# BengalaV1.net
KiCad netlist of a schematic drawn in EAGLE
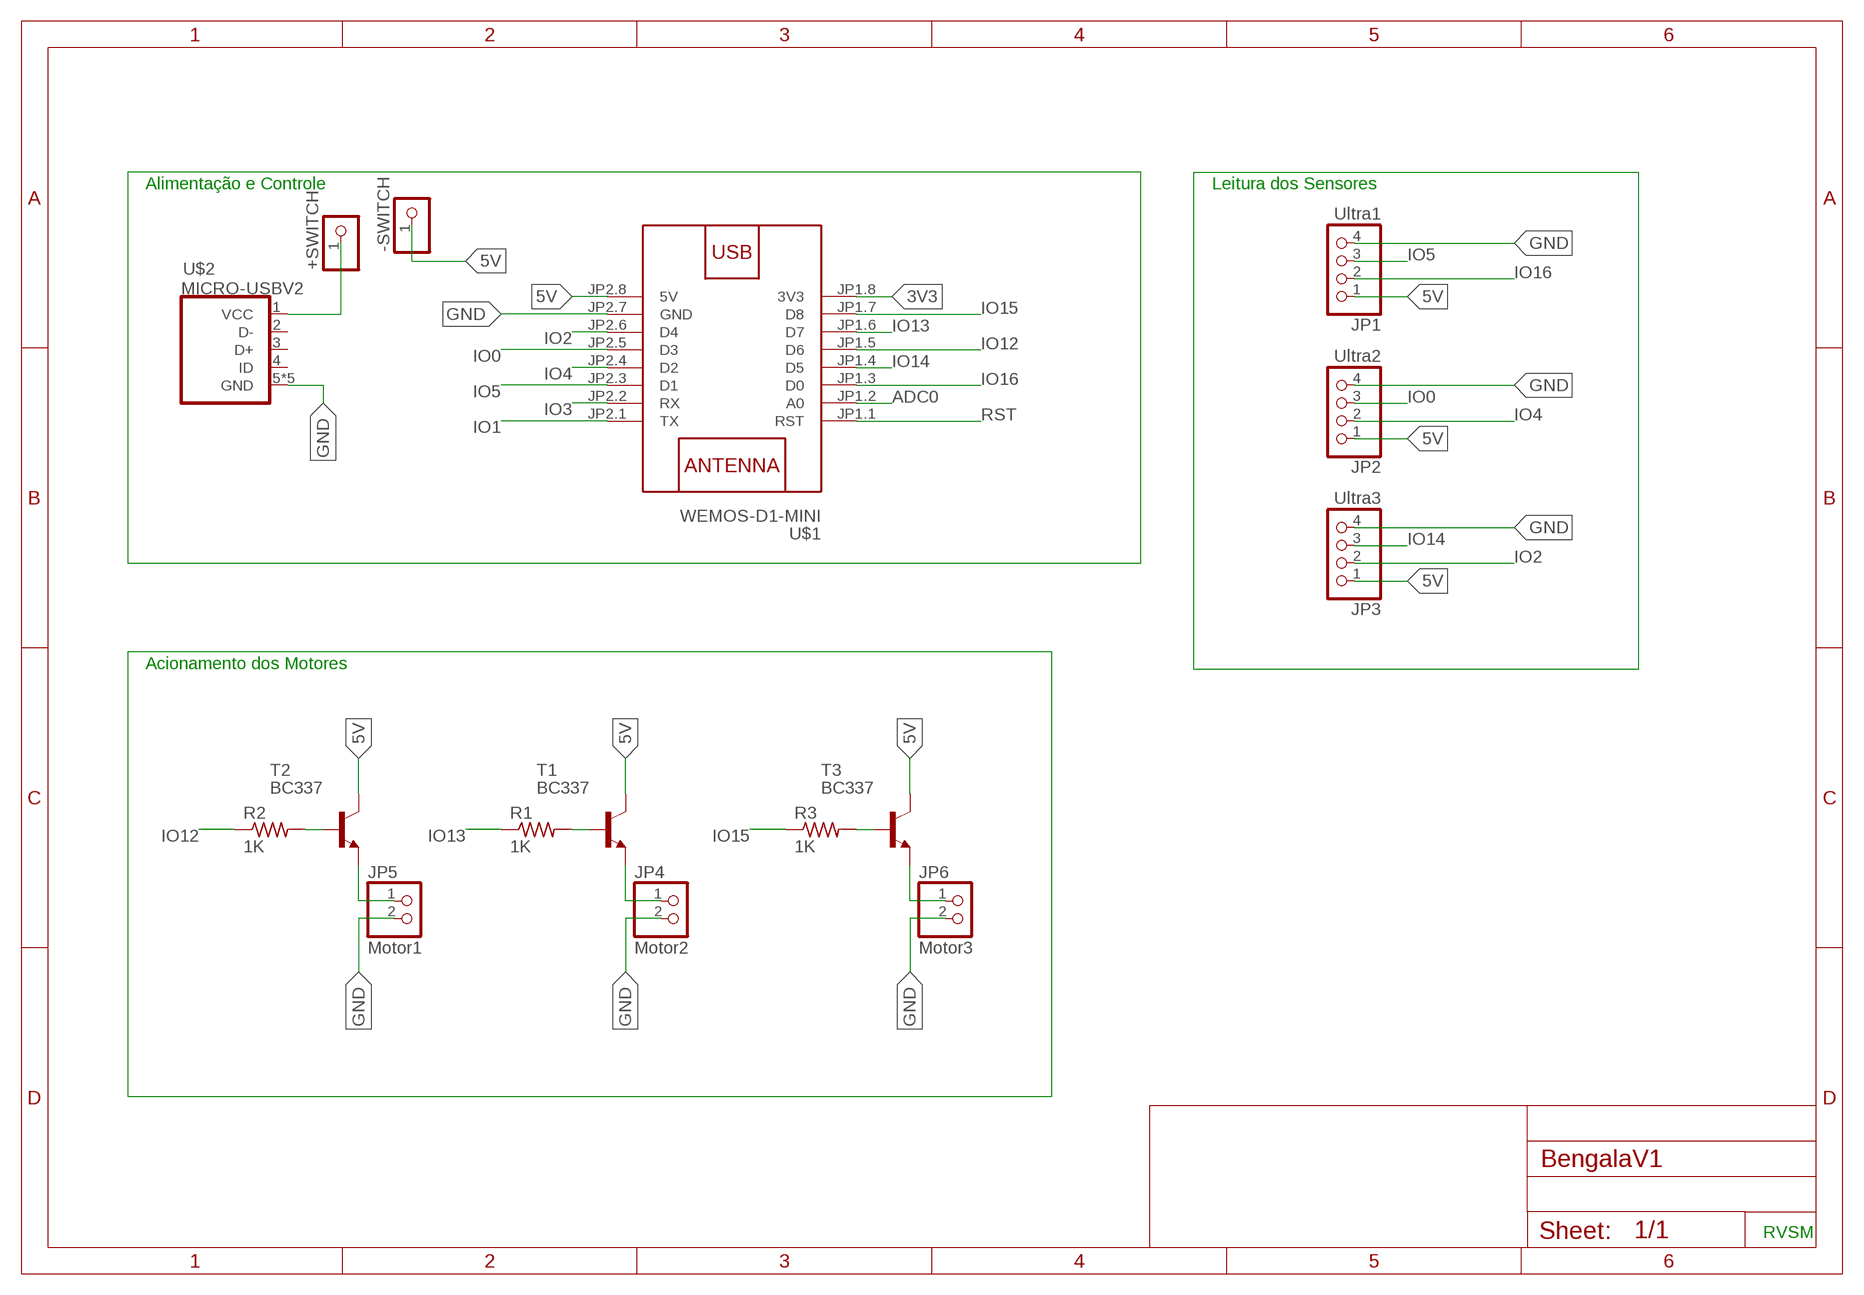
[diagram p0: schematic, sheet 1]

(export (version "E")
  (design (tool "Eeschema 10.0.6"))
  (components
    (comp (ref "+SWITCH")
      (value "PINHD-1X1")
      (footprint "eagle-import:1X01")
      (libsource (lib "eagle-import") (part "PINHD-1X1"))
    )
    (comp (ref "-SWITCH")
      (value "PINHD-1X1")
      (footprint "eagle-import:1X01")
      (libsource (lib "eagle-import") (part "PINHD-1X1"))
    )
    (comp (ref "JP1")
      (value "Ultra1")
      (footprint "eagle-import:1X04")
      (libsource (lib "eagle-import") (part "PINHD-1X4"))
    )
    (comp (ref "JP2")
      (value "Ultra2")
      (footprint "eagle-import:1X04")
      (libsource (lib "eagle-import") (part "PINHD-1X4"))
    )
    (comp (ref "JP3")
      (value "Ultra3")
      (footprint "eagle-import:1X04")
      (libsource (lib "eagle-import") (part "PINHD-1X4"))
    )
    (comp (ref "JP4")
      (value "Motor2")
      (footprint "eagle-import:1X02")
      (libsource (lib "eagle-import") (part "PINHD-1X2"))
    )
    (comp (ref "JP5")
      (value "Motor1")
      (footprint "eagle-import:1X02")
      (libsource (lib "eagle-import") (part "PINHD-1X2"))
    )
    (comp (ref "JP6")
      (value "Motor3")
      (footprint "eagle-import:1X02")
      (libsource (lib "eagle-import") (part "PINHD-1X2"))
    )
    (comp (ref "R1")
      (value "1K")
      (footprint "eagle-import:0204_7")
      (libsource (lib "eagle-import") (part "R-US_0204/7"))
    )
    (comp (ref "R2")
      (value "1K")
      (footprint "eagle-import:0204_7")
      (libsource (lib "eagle-import") (part "R-US_0204/7"))
    )
    (comp (ref "R3")
      (value "1K")
      (footprint "eagle-import:0204_7")
      (libsource (lib "eagle-import") (part "R-US_0204/7"))
    )
    (comp (ref "T1")
      (value "BC337")
      (footprint "eagle-import:TO92")
      (libsource (lib "eagle-import") (part "BC337"))
    )
    (comp (ref "T2")
      (value "BC337")
      (footprint "eagle-import:TO92")
      (libsource (lib "eagle-import") (part "BC337"))
    )
    (comp (ref "T3")
      (value "BC337")
      (footprint "eagle-import:TO92")
      (libsource (lib "eagle-import") (part "BC337"))
    )
    (comp (ref "U$1")
      (value "WEMOS-D1-MINI")
      (footprint "eagle-import:WEMOS-D1-MINI")
      (libsource (lib "eagle-import") (part "WEMOS-D1-MINI"))
    )
    (comp (ref "U$2")
      (value "MICRO-USBV2")
      (footprint "eagle-import:MICRO-USB-2")
      (libsource (lib "eagle-import") (part "MICRO-USBV2"))
    )
  )
  (nets
    (net (code "1") (name "/ADC0") (class "Default")
      (node (ref "U$1") (pin "JP1.2") (pinfunction "A0_JP1.2") (pintype "bidirectional"))
    )
    (net (code "2") (name "/IO0") (class "Default")
      (node (ref "JP2") (pin "3") (pinfunction "3_3") (pintype "passive"))
      (node (ref "U$1") (pin "JP2.5") (pinfunction "D3_JP2.5") (pintype "bidirectional"))
    )
    (net (code "3") (name "/IO1") (class "Default")
      (node (ref "U$1") (pin "JP2.1") (pinfunction "TX_JP2.1") (pintype "bidirectional"))
    )
    (net (code "4") (name "/IO2") (class "Default")
      (node (ref "JP3") (pin "2") (pinfunction "2_2") (pintype "passive"))
      (node (ref "U$1") (pin "JP2.6") (pinfunction "D4_JP2.6") (pintype "bidirectional"))
    )
    (net (code "5") (name "/IO3") (class "Default")
      (node (ref "U$1") (pin "JP2.2") (pinfunction "RX_JP2.2") (pintype "bidirectional"))
    )
    (net (code "6") (name "/IO4") (class "Default")
      (node (ref "JP2") (pin "2") (pinfunction "2_2") (pintype "passive"))
      (node (ref "U$1") (pin "JP2.4") (pinfunction "D2_JP2.4") (pintype "bidirectional"))
    )
    (net (code "7") (name "/IO5") (class "Default")
      (node (ref "JP1") (pin "3") (pinfunction "3_3") (pintype "passive"))
      (node (ref "U$1") (pin "JP2.3") (pinfunction "D1_JP2.3") (pintype "bidirectional"))
    )
    (net (code "8") (name "/IO12") (class "Default")
      (node (ref "R2") (pin "1") (pinfunction "1_1") (pintype "passive"))
      (node (ref "U$1") (pin "JP1.5") (pinfunction "D6_JP1.5") (pintype "bidirectional"))
    )
    (net (code "9") (name "/IO13") (class "Default")
      (node (ref "R1") (pin "1") (pinfunction "1_1") (pintype "passive"))
      (node (ref "U$1") (pin "JP1.6") (pinfunction "D7_JP1.6") (pintype "bidirectional"))
    )
    (net (code "10") (name "/IO14") (class "Default")
      (node (ref "JP3") (pin "3") (pinfunction "3_3") (pintype "passive"))
      (node (ref "U$1") (pin "JP1.4") (pinfunction "D5_JP1.4") (pintype "bidirectional"))
    )
    (net (code "11") (name "/IO15") (class "Default")
      (node (ref "R3") (pin "1") (pinfunction "1_1") (pintype "passive"))
      (node (ref "U$1") (pin "JP1.7") (pinfunction "D8_JP1.7") (pintype "bidirectional"))
    )
    (net (code "12") (name "/IO16") (class "Default")
      (node (ref "JP1") (pin "2") (pinfunction "2_2") (pintype "passive"))
      (node (ref "U$1") (pin "JP1.3") (pinfunction "D0_JP1.3") (pintype "bidirectional"))
    )
    (net (code "13") (name "/RST") (class "Default")
      (node (ref "U$1") (pin "JP1.1") (pinfunction "RST_JP1.1") (pintype "bidirectional"))
    )
    (net (code "14") (name "3V3") (class "Default")
      (node (ref "U$1") (pin "JP1.8") (pinfunction "3V3_JP1.8") (pintype "power_in"))
    )
    (net (code "15") (name "5V") (class "Default")
      (node (ref "-SWITCH") (pin "1") (pinfunction "1_1") (pintype "passive"))
      (node (ref "JP1") (pin "1") (pinfunction "1_1") (pintype "passive"))
      (node (ref "JP2") (pin "1") (pinfunction "1_1") (pintype "passive"))
      (node (ref "JP3") (pin "1") (pinfunction "1_1") (pintype "passive"))
      (node (ref "T1") (pin "3") (pinfunction "C_3") (pintype "passive"))
      (node (ref "T2") (pin "3") (pinfunction "C_3") (pintype "passive"))
      (node (ref "T3") (pin "3") (pinfunction "C_3") (pintype "passive"))
      (node (ref "U$1") (pin "JP2.8") (pinfunction "5V_JP2.8") (pintype "power_in"))
    )
    (net (code "16") (name "GND") (class "Default")
      (node (ref "JP1") (pin "4") (pinfunction "4_4") (pintype "passive"))
      (node (ref "JP2") (pin "4") (pinfunction "4_4") (pintype "passive"))
      (node (ref "JP3") (pin "4") (pinfunction "4_4") (pintype "passive"))
      (node (ref "JP4") (pin "2") (pinfunction "2_2") (pintype "passive"))
      (node (ref "JP5") (pin "2") (pinfunction "2_2") (pintype "passive"))
      (node (ref "JP6") (pin "2") (pinfunction "2_2") (pintype "passive"))
      (node (ref "U$1") (pin "JP2.7") (pinfunction "GND_JP2.7") (pintype "power_in"))
      (node (ref "U$2") (pin "5") (pinfunction "GND_5") (pintype "power_in"))
      (node (ref "U$2") (pin "P$1") (pinfunction "GND_P$1") (pintype "power_in"))
      (node (ref "U$2") (pin "P$2") (pinfunction "GND_P$2") (pintype "power_in"))
      (node (ref "U$2") (pin "P$3") (pinfunction "GND_P$3") (pintype "power_in"))
      (node (ref "U$2") (pin "P$4") (pinfunction "GND_P$4") (pintype "power_in"))
    )
    (net (code "17") (name "Net-(T1-B)") (class "Default")
      (node (ref "R1") (pin "2") (pinfunction "2_2") (pintype "passive"))
      (node (ref "T1") (pin "2") (pinfunction "B_2") (pintype "passive"))
    )
    (net (code "18") (name "Net-(T1-E)") (class "Default")
      (node (ref "JP4") (pin "1") (pinfunction "1_1") (pintype "passive"))
      (node (ref "T1") (pin "1") (pinfunction "E_1") (pintype "passive"))
    )
    (net (code "19") (name "Net-(T2-B)") (class "Default")
      (node (ref "R2") (pin "2") (pinfunction "2_2") (pintype "passive"))
      (node (ref "T2") (pin "2") (pinfunction "B_2") (pintype "passive"))
    )
    (net (code "20") (name "Net-(T2-E)") (class "Default")
      (node (ref "JP5") (pin "1") (pinfunction "1_1") (pintype "passive"))
      (node (ref "T2") (pin "1") (pinfunction "E_1") (pintype "passive"))
    )
    (net (code "21") (name "Net-(T3-B)") (class "Default")
      (node (ref "R3") (pin "2") (pinfunction "2_2") (pintype "passive"))
      (node (ref "T3") (pin "2") (pinfunction "B_2") (pintype "passive"))
    )
    (net (code "22") (name "Net-(T3-E)") (class "Default")
      (node (ref "JP6") (pin "1") (pinfunction "1_1") (pintype "passive"))
      (node (ref "T3") (pin "1") (pinfunction "E_1") (pintype "passive"))
    )
    (net (code "23") (name "Net-(U$2-VCC)") (class "Default")
      (node (ref "+SWITCH") (pin "1") (pinfunction "1_1") (pintype "passive"))
      (node (ref "U$2") (pin "1") (pinfunction "VCC_1") (pintype "power_in"))
    )
    (net (code "24") (name "unconnected-(U$2-D+-Pad3)") (class "Default")
      (node (ref "U$2") (pin "3") (pinfunction "D+_3") (pintype "bidirectional"))
    )
    (net (code "25") (name "unconnected-(U$2-D--Pad2)") (class "Default")
      (node (ref "U$2") (pin "2") (pinfunction "D-_2") (pintype "bidirectional"))
    )
    (net (code "26") (name "unconnected-(U$2-ID-Pad4)") (class "Default")
      (node (ref "U$2") (pin "4") (pinfunction "ID_4") (pintype "bidirectional"))
    )
  )
)
